# football_main_board_2016.net
KiCad netlist of a schematic drawn in Altium Designer
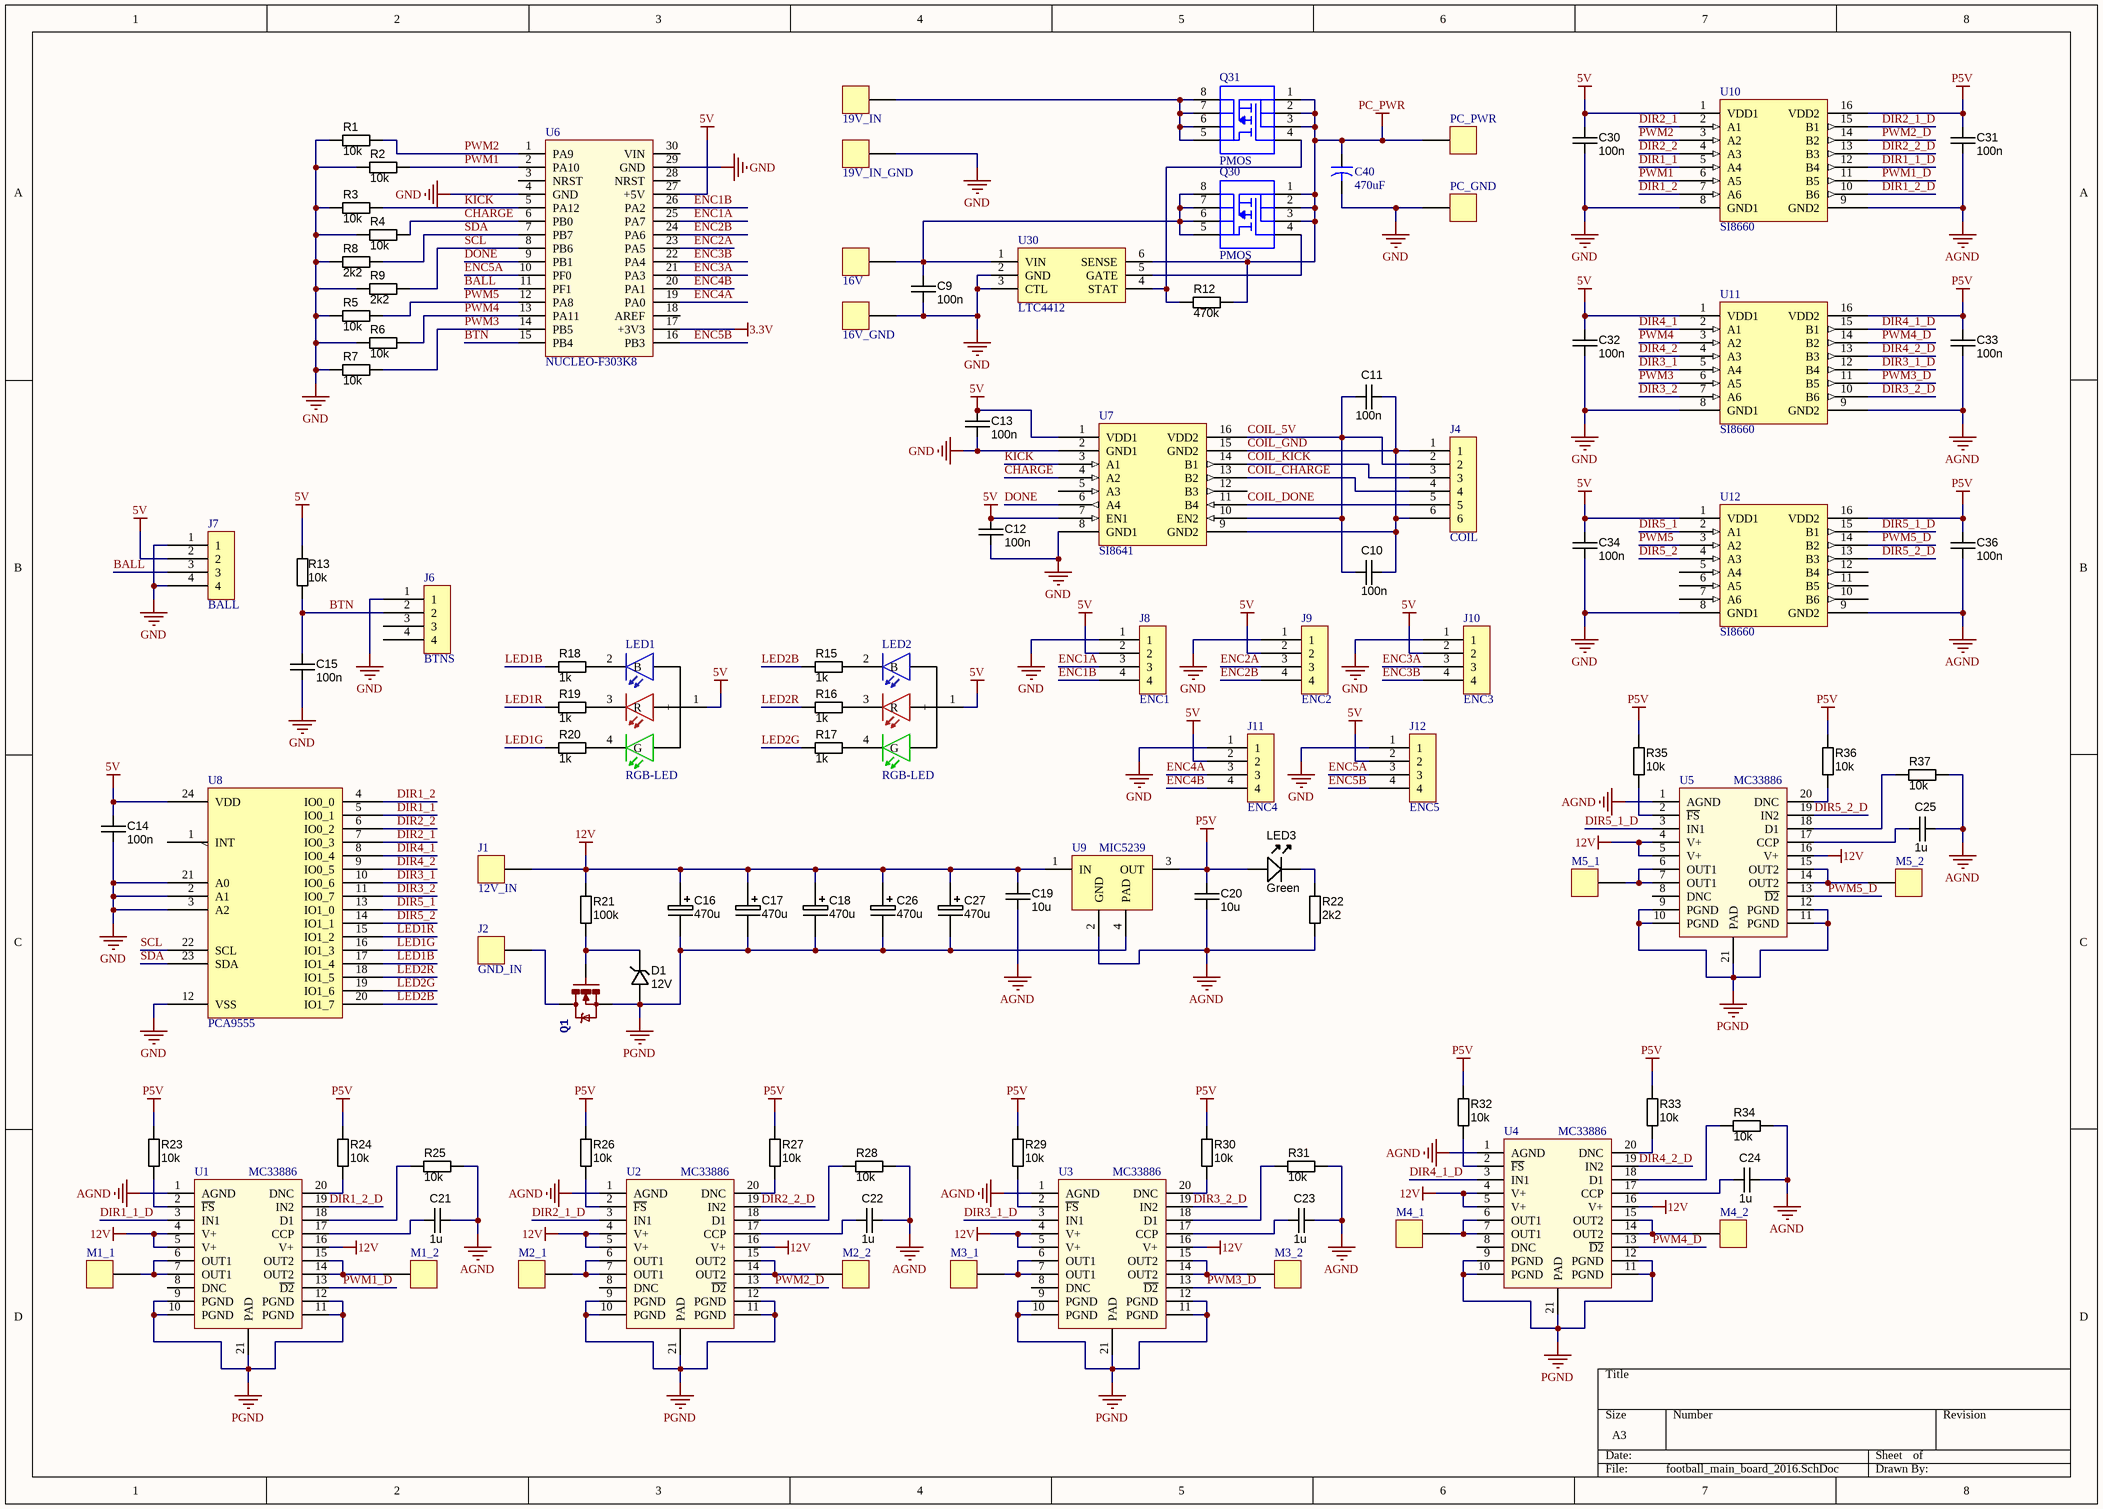
[diagram p0: football_main_board_2016.SchDoc]

(export (version "E")
  (design (tool "Eeschema 10.0.6"))
  (components
    (comp (ref "16V") (value "HEADER-1") (footprint "POWER-PAD-4x3") (libsource (lib "") (part "HEADER-1_1")))
    (comp (ref "16V_GND")
      (value "HEADER-1")
      (footprint "POWER-PAD-4x3")
      (libsource (lib "") (part "HEADER-1_1"))
    )
    (comp (ref "19V_IN")
      (value "HEADER-1")
      (footprint "POWER-PAD-4x3")
      (libsource (lib "") (part "HEADER-1_1"))
    )
    (comp (ref "19V_IN_GND")
      (value "HEADER-1")
      (footprint "POWER-PAD-4x3")
      (libsource (lib "") (part "HEADER-1_1"))
    )
    (comp (ref "C9")
      (value "100n")
      (footprint "CAPC1608X90N")
      (description "Capacitor SMD Cer 10nF 10% 50V X7R 0603")
      (fields (field (name "TOLERANCE") "±10%"))
      (libsource (lib "PBL - Capacitors") (part "CAPC_10n_0603_X7R_50V_10%"))
    )
    (comp (ref "C10")
      (value "100n")
      (footprint "CAPC1608X90N")
      (description "Capacitor SMD Cer 10nF 10% 50V X7R 0603")
      (fields (field (name "TOLERANCE") "±10%"))
      (libsource (lib "PBL - Capacitors") (part "CAPC_10n_0603_X7R_50V_10%"))
    )
    (comp (ref "C11")
      (value "100n")
      (footprint "CAPC1608X90N")
      (description "Capacitor SMD Cer 10nF 10% 50V X7R 0603")
      (fields (field (name "TOLERANCE") "±10%"))
      (libsource (lib "PBL - Capacitors") (part "CAPC_10n_0603_X7R_50V_10%"))
    )
    (comp (ref "C12")
      (value "100n")
      (footprint "CAPC1608X90N")
      (description "Capacitor SMD Cer 10nF 10% 50V X7R 0603")
      (fields (field (name "TOLERANCE") "±10%"))
      (libsource (lib "PBL - Capacitors") (part "CAPC_10n_0603_X7R_50V_10%"))
    )
    (comp (ref "C13")
      (value "100n")
      (footprint "CAPC1608X90N")
      (description "Capacitor SMD Cer 10nF 10% 50V X7R 0603")
      (fields (field (name "TOLERANCE") "±10%"))
      (libsource (lib "PBL - Capacitors") (part "CAPC_10n_0603_X7R_50V_10%"))
    )
    (comp (ref "C14")
      (value "100n")
      (footprint "CAPC1608X90N")
      (description "Capacitor SMD Cer 10nF 10% 50V X7R 0603")
      (fields (field (name "TOLERANCE") "±10%"))
      (libsource (lib "PBL - Capacitors") (part "CAPC_10n_0603_X7R_50V_10%"))
    )
    (comp (ref "C15")
      (value "100n")
      (footprint "CAPC1608X90N")
      (description "Capacitor SMD Cer 10nF 10% 50V X7R 0603")
      (fields (field (name "TOLERANCE") "±10%"))
      (libsource (lib "PBL - Capacitors") (part "CAPC_10n_0603_X7R_50V_10%"))
    )
    (comp (ref "C16")
      (value "470u")
      (footprint "CAP-LEADED-SMD-5")
      (libsource (lib "misc") (part "CAP-ELEC"))
    )
    (comp (ref "C17")
      (value "470u")
      (footprint "CAP-LEADED-SMD-5")
      (libsource (lib "misc") (part "CAP-ELEC"))
    )
    (comp (ref "C18")
      (value "470u")
      (footprint "CAP-LEADED-SMD-5")
      (libsource (lib "misc") (part "CAP-ELEC"))
    )
    (comp (ref "C19")
      (value "10u")
      (footprint "CAPC3216X180N")
      (description "Capacitor SMD Cer 10uF 10% 16V X7R 1206")
      (fields (field (name "TOLERANCE") "±10%"))
      (libsource (lib "PBL - Capacitors") (part "CAPC_10u_1206_16V"))
    )
    (comp (ref "C20")
      (value "10u")
      (footprint "CAPC3216X180N")
      (description "Capacitor SMD Cer 10uF 10% 16V X7R 1206")
      (fields (field (name "TOLERANCE") "±10%"))
      (libsource (lib "PBL - Capacitors") (part "CAPC_10u_1206_16V"))
    )
    (comp (ref "C21")
      (value "1u")
      (footprint "CAPC1608X90N")
      (description "Capacitor SMD Cer 10nF 10% 50V X7R 0603")
      (fields (field (name "TOLERANCE") "±10%"))
      (libsource (lib "PBL - Capacitors") (part "CAPC_10n_0603_X7R_50V_10%"))
    )
    (comp (ref "C22")
      (value "1u")
      (footprint "CAPC1608X90N")
      (description "Capacitor SMD Cer 10nF 10% 50V X7R 0603")
      (fields (field (name "TOLERANCE") "±10%"))
      (libsource (lib "PBL - Capacitors") (part "CAPC_10n_0603_X7R_50V_10%"))
    )
    (comp (ref "C23")
      (value "1u")
      (footprint "CAPC1608X90N")
      (description "Capacitor SMD Cer 10nF 10% 50V X7R 0603")
      (fields (field (name "TOLERANCE") "±10%"))
      (libsource (lib "PBL - Capacitors") (part "CAPC_10n_0603_X7R_50V_10%"))
    )
    (comp (ref "C24")
      (value "1u")
      (footprint "CAPC1608X90N")
      (description "Capacitor SMD Cer 10nF 10% 50V X7R 0603")
      (fields (field (name "TOLERANCE") "±10%"))
      (libsource (lib "PBL - Capacitors") (part "CAPC_10n_0603_X7R_50V_10%"))
    )
    (comp (ref "C25")
      (value "1u")
      (footprint "CAPC1608X90N")
      (description "Capacitor SMD Cer 10nF 10% 50V X7R 0603")
      (fields (field (name "TOLERANCE") "±10%"))
      (libsource (lib "PBL - Capacitors") (part "CAPC_10n_0603_X7R_50V_10%"))
    )
    (comp (ref "C26")
      (value "470u")
      (footprint "CAP-LEADED-SMD-5")
      (libsource (lib "misc") (part "CAP-ELEC"))
    )
    (comp (ref "C27")
      (value "470u")
      (footprint "CAP-LEADED-SMD-5")
      (libsource (lib "misc") (part "CAP-ELEC"))
    )
    (comp (ref "C30")
      (value "100n")
      (footprint "CAPC1608X90N")
      (description "Capacitor SMD Cer 10nF 10% 50V X7R 0603")
      (fields (field (name "TOLERANCE") "±10%"))
      (libsource (lib "PBL - Capacitors") (part "CAPC_10n_0603_X7R_50V_10%"))
    )
    (comp (ref "C31")
      (value "100n")
      (footprint "CAPC1608X90N")
      (description "Capacitor SMD Cer 10nF 10% 50V X7R 0603")
      (fields (field (name "TOLERANCE") "±10%"))
      (libsource (lib "PBL - Capacitors") (part "CAPC_10n_0603_X7R_50V_10%"))
    )
    (comp (ref "C32")
      (value "100n")
      (footprint "CAPC1608X90N")
      (description "Capacitor SMD Cer 10nF 10% 50V X7R 0603")
      (fields (field (name "TOLERANCE") "±10%"))
      (libsource (lib "PBL - Capacitors") (part "CAPC_10n_0603_X7R_50V_10%"))
    )
    (comp (ref "C33")
      (value "100n")
      (footprint "CAPC1608X90N")
      (description "Capacitor SMD Cer 10nF 10% 50V X7R 0603")
      (fields (field (name "TOLERANCE") "±10%"))
      (libsource (lib "PBL - Capacitors") (part "CAPC_10n_0603_X7R_50V_10%"))
    )
    (comp (ref "C34")
      (value "100n")
      (footprint "CAPC1608X90N")
      (description "Capacitor SMD Cer 10nF 10% 50V X7R 0603")
      (fields (field (name "TOLERANCE") "±10%"))
      (libsource (lib "PBL - Capacitors") (part "CAPC_10n_0603_X7R_50V_10%"))
    )
    (comp (ref "C36")
      (value "100n")
      (footprint "CAPC1608X90N")
      (description "Capacitor SMD Cer 10nF 10% 50V X7R 0603")
      (fields (field (name "TOLERANCE") "±10%"))
      (libsource (lib "PBL - Capacitors") (part "CAPC_10n_0603_X7R_50V_10%"))
    )
    (comp (ref "C40")
      (value "470uF")
      (footprint "CAPR5-4X5")
      (description "Capacitor")
      (fields (field (name "PUBLISHER") "Altium Limited"))
      (libsource (lib "Miscellaneous Devices") (part "Cap2"))
    )
    (comp (ref "D1")
      (value "12V")
      (footprint "SOD123")
      (description "Diode Zener SMD 28V 0.5W SOD-123")
      (fields (field (name "TOLERANCE") "±5%"))
      (libsource (lib "PBL - Diodes") (part "DIODE_ZENER_28V_500mW"))
    )
    (comp (ref "J1") (value "12V_IN") (footprint "POWER-PAD") (libsource (lib "") (part "HEADER-1_1")))
    (comp (ref "J2") (value "GND_IN") (footprint "POWER-PAD") (libsource (lib "") (part "HEADER-1_1")))
    (comp (ref "J4")
      (value "COIL")
      (footprint "MICRO-MATCH-6")
      (libsource (lib "connectors") (part "HEADER-6"))
    )
    (comp (ref "J6")
      (value "BTNS")
      (footprint "MICRO-MATCH-4")
      (libsource (lib "connectors") (part "HEADER-4"))
    )
    (comp (ref "J7")
      (value "BALL")
      (footprint "MICRO-MATCH-4")
      (libsource (lib "connectors") (part "HEADER-4"))
    )
    (comp (ref "J8")
      (value "ENC1")
      (footprint "MICRO-MATCH-4")
      (libsource (lib "connectors") (part "HEADER-4"))
    )
    (comp (ref "J9")
      (value "ENC2")
      (footprint "MICRO-MATCH-4")
      (libsource (lib "connectors") (part "HEADER-4"))
    )
    (comp (ref "J10")
      (value "ENC3")
      (footprint "MICRO-MATCH-4")
      (libsource (lib "connectors") (part "HEADER-4"))
    )
    (comp (ref "J11")
      (value "ENC4")
      (footprint "MICRO-MATCH-4")
      (libsource (lib "connectors") (part "HEADER-4"))
    )
    (comp (ref "J12")
      (value "ENC5")
      (footprint "MICRO-MATCH-4")
      (libsource (lib "connectors") (part "HEADER-4"))
    )
    (comp (ref "LED1") (value "RGB-LED") (footprint "RGB-LED") (libsource (lib "misc") (part "RGB-LED")))
    (comp (ref "LED2") (value "RGB-LED") (footprint "RGB-LED") (libsource (lib "misc") (part "RGB-LED")))
    (comp (ref "LED3")
      (value "Green")
      (footprint "LED-0603-GREEN")
      (description "LED 0603 SMD Green 570nm 50mcd 20mA")
      (libsource (lib "PBL - Light Sources") (part "LED_SMD_Green_0603_570nm"))
    )
    (comp (ref "M1_1")
      (value "HEADER-1")
      (footprint "POWER-PAD-4x3")
      (libsource (lib "") (part "HEADER-1_1"))
    )
    (comp (ref "M1_2")
      (value "HEADER-1")
      (footprint "POWER-PAD-4x3")
      (libsource (lib "connectors") (part "HEADER-1"))
    )
    (comp (ref "M2_1")
      (value "HEADER-1")
      (footprint "POWER-PAD-4x3")
      (libsource (lib "") (part "HEADER-1_1"))
    )
    (comp (ref "M2_2")
      (value "HEADER-1")
      (footprint "POWER-PAD-4x3")
      (libsource (lib "connectors") (part "HEADER-1"))
    )
    (comp (ref "M3_1")
      (value "HEADER-1")
      (footprint "POWER-PAD-4x3")
      (libsource (lib "") (part "HEADER-1_1"))
    )
    (comp (ref "M3_2")
      (value "HEADER-1")
      (footprint "POWER-PAD-4x3")
      (libsource (lib "connectors") (part "HEADER-1"))
    )
    (comp (ref "M4_1")
      (value "HEADER-1")
      (footprint "POWER-PAD-4x3")
      (libsource (lib "") (part "HEADER-1_1"))
    )
    (comp (ref "M4_2")
      (value "HEADER-1")
      (footprint "POWER-PAD-4x3")
      (libsource (lib "connectors") (part "HEADER-1"))
    )
    (comp (ref "M5_1")
      (value "HEADER-1")
      (footprint "POWER-PAD-4x3")
      (libsource (lib "") (part "HEADER-1_1"))
    )
    (comp (ref "M5_2")
      (value "HEADER-1")
      (footprint "POWER-PAD-4x3")
      (libsource (lib "connectors") (part "HEADER-1"))
    )
    (comp (ref "PC_GND")
      (value "HEADER-1")
      (footprint "POWER-PAD-4x3")
      (libsource (lib "connectors") (part "HEADER-1"))
    )
    (comp (ref "PC_PWR")
      (value "HEADER-1")
      (footprint "POWER-PAD-4x3")
      (libsource (lib "connectors") (part "HEADER-1"))
    )
    (comp (ref "Q1") (value "MOSFET-N") (footprint "SOT669") (libsource (lib "mosfets") (part "MOSFET-N")))
    (comp (ref "Q30") (value "PMOS") (footprint "SO8") (libsource (lib "misc") (part "PMOS")))
    (comp (ref "Q31") (value "PMOS") (footprint "SO8") (libsource (lib "misc") (part "PMOS")))
    (comp (ref "R1")
      (value "10k")
      (footprint "RESC1608X55N")
      (description "Resistor SMD chip 10k Ohm 0.1W 1% 0603")
      (fields (field (name "TOLERANCE") "±1%"))
      (libsource (lib "PBL - Resistors") (part "RES_10K_0603_1%"))
    )
    (comp (ref "R2")
      (value "10k")
      (footprint "RESC1608X55N")
      (description "Resistor SMD chip 10k Ohm 0.1W 1% 0603")
      (fields (field (name "TOLERANCE") "±1%"))
      (libsource (lib "PBL - Resistors") (part "RES_10K_0603_1%"))
    )
    (comp (ref "R3")
      (value "10k")
      (footprint "RESC1608X55N")
      (description "Resistor SMD chip 10k Ohm 0.1W 1% 0603")
      (fields (field (name "TOLERANCE") "±1%"))
      (libsource (lib "PBL - Resistors") (part "RES_10K_0603_1%"))
    )
    (comp (ref "R4")
      (value "10k")
      (footprint "RESC1608X55N")
      (description "Resistor SMD chip 10k Ohm 0.1W 1% 0603")
      (fields (field (name "TOLERANCE") "±1%"))
      (libsource (lib "PBL - Resistors") (part "RES_10K_0603_1%"))
    )
    (comp (ref "R5")
      (value "10k")
      (footprint "RESC1608X55N")
      (description "Resistor SMD chip 10k Ohm 0.1W 1% 0603")
      (fields (field (name "TOLERANCE") "±1%"))
      (libsource (lib "PBL - Resistors") (part "RES_10K_0603_1%"))
    )
    (comp (ref "R6")
      (value "10k")
      (footprint "RESC1608X55N")
      (description "Resistor SMD chip 10k Ohm 0.1W 1% 0603")
      (fields (field (name "TOLERANCE") "±1%"))
      (libsource (lib "PBL - Resistors") (part "RES_10K_0603_1%"))
    )
    (comp (ref "R7")
      (value "10k")
      (footprint "RESC1608X55N")
      (description "Resistor SMD chip 10k Ohm 0.1W 1% 0603")
      (fields (field (name "TOLERANCE") "±1%"))
      (libsource (lib "PBL - Resistors") (part "RES_10K_0603_1%"))
    )
    (comp (ref "R8")
      (value "2k2")
      (footprint "RESC1608X55N")
      (description "Resistor SMD chip 10k Ohm 0.1W 1% 0603")
      (fields (field (name "TOLERANCE") "±1%"))
      (libsource (lib "PBL - Resistors") (part "RES_10K_0603_1%"))
    )
    (comp (ref "R9")
      (value "2k2")
      (footprint "RESC1608X55N")
      (description "Resistor SMD chip 10k Ohm 0.1W 1% 0603")
      (fields (field (name "TOLERANCE") "±1%"))
      (libsource (lib "PBL - Resistors") (part "RES_10K_0603_1%"))
    )
    (comp (ref "R12")
      (value "470k")
      (footprint "RESC1608N_ZERO")
      (description "Resistor SMD chip 0.0 Ohm 0.1W 0603")
      (fields (field (name "TOLERANCE") "±5%"))
      (libsource (lib "PBL - Resistors") (part "RES_0R_0603"))
    )
    (comp (ref "R13")
      (value "10k")
      (footprint "RESC1608N_ZERO")
      (description "Resistor SMD chip 0.0 Ohm 0.1W 0603")
      (fields (field (name "TOLERANCE") "±5%"))
      (libsource (lib "") (part "RES_0R_0603_1"))
    )
    (comp (ref "R15")
      (value "1k")
      (footprint "RESC1608N_ZERO")
      (description "Resistor SMD chip 0.0 Ohm 0.1W 0603")
      (fields (field (name "TOLERANCE") "±5%"))
      (libsource (lib "PBL - Resistors") (part "RES_0R_0603"))
    )
    (comp (ref "R16")
      (value "1k")
      (footprint "RESC1608N_ZERO")
      (description "Resistor SMD chip 0.0 Ohm 0.1W 0603")
      (fields (field (name "TOLERANCE") "±5%"))
      (libsource (lib "PBL - Resistors") (part "RES_0R_0603"))
    )
    (comp (ref "R17")
      (value "1k")
      (footprint "RESC1608N_ZERO")
      (description "Resistor SMD chip 0.0 Ohm 0.1W 0603")
      (fields (field (name "TOLERANCE") "±5%"))
      (libsource (lib "PBL - Resistors") (part "RES_0R_0603"))
    )
    (comp (ref "R18")
      (value "1k")
      (footprint "RESC1608N_ZERO")
      (description "Resistor SMD chip 0.0 Ohm 0.1W 0603")
      (fields (field (name "TOLERANCE") "±5%"))
      (libsource (lib "PBL - Resistors") (part "RES_0R_0603"))
    )
    (comp (ref "R19")
      (value "1k")
      (footprint "RESC1608N_ZERO")
      (description "Resistor SMD chip 0.0 Ohm 0.1W 0603")
      (fields (field (name "TOLERANCE") "±5%"))
      (libsource (lib "PBL - Resistors") (part "RES_0R_0603"))
    )
    (comp (ref "R20")
      (value "1k")
      (footprint "RESC1608N_ZERO")
      (description "Resistor SMD chip 0.0 Ohm 0.1W 0603")
      (fields (field (name "TOLERANCE") "±5%"))
      (libsource (lib "PBL - Resistors") (part "RES_0R_0603"))
    )
    (comp (ref "R21")
      (value "100k")
      (footprint "RESC1608X55N")
      (description "Resistor SMD chip 1k Ohm 0.1W 1% 0603")
      (fields (field (name "TOLERANCE") "±1%"))
      (libsource (lib "") (part "RES_1K_0603_1%_1"))
    )
    (comp (ref "R22")
      (value "2k2")
      (footprint "RESC1608X55N")
      (description "Resistor SMD chip 1k Ohm 0.1W 1% 0603")
      (fields (field (name "TOLERANCE") "±1%"))
      (libsource (lib "") (part "RES_1K_0603_1%_1"))
    )
    (comp (ref "R23")
      (value "10k")
      (footprint "RESC1608X55N")
      (description "Resistor SMD chip 1k Ohm 0.1W 1% 0603")
      (fields (field (name "TOLERANCE") "±1%"))
      (libsource (lib "") (part "RES_1K_0603_1%_1"))
    )
    (comp (ref "R24")
      (value "10k")
      (footprint "RESC1608X55N")
      (description "Resistor SMD chip 1k Ohm 0.1W 1% 0603")
      (fields (field (name "TOLERANCE") "±1%"))
      (libsource (lib "") (part "RES_1K_0603_1%_1"))
    )
    (comp (ref "R25")
      (value "10k")
      (footprint "RESC1608X55N")
      (description "Resistor SMD chip 1k Ohm 0.1W 1% 0603")
      (fields (field (name "TOLERANCE") "±1%"))
      (libsource (lib "PBL - Resistors") (part "RES_1K_0603_1%"))
    )
    (comp (ref "R26")
      (value "10k")
      (footprint "RESC1608X55N")
      (description "Resistor SMD chip 1k Ohm 0.1W 1% 0603")
      (fields (field (name "TOLERANCE") "±1%"))
      (libsource (lib "") (part "RES_1K_0603_1%_1"))
    )
    (comp (ref "R27")
      (value "10k")
      (footprint "RESC1608X55N")
      (description "Resistor SMD chip 1k Ohm 0.1W 1% 0603")
      (fields (field (name "TOLERANCE") "±1%"))
      (libsource (lib "") (part "RES_1K_0603_1%_1"))
    )
    (comp (ref "R28")
      (value "10k")
      (footprint "RESC1608X55N")
      (description "Resistor SMD chip 1k Ohm 0.1W 1% 0603")
      (fields (field (name "TOLERANCE") "±1%"))
      (libsource (lib "PBL - Resistors") (part "RES_1K_0603_1%"))
    )
    (comp (ref "R29")
      (value "10k")
      (footprint "RESC1608X55N")
      (description "Resistor SMD chip 1k Ohm 0.1W 1% 0603")
      (fields (field (name "TOLERANCE") "±1%"))
      (libsource (lib "") (part "RES_1K_0603_1%_1"))
    )
    (comp (ref "R30")
      (value "10k")
      (footprint "RESC1608X55N")
      (description "Resistor SMD chip 1k Ohm 0.1W 1% 0603")
      (fields (field (name "TOLERANCE") "±1%"))
      (libsource (lib "") (part "RES_1K_0603_1%_1"))
    )
    (comp (ref "R31")
      (value "10k")
      (footprint "RESC1608X55N")
      (description "Resistor SMD chip 1k Ohm 0.1W 1% 0603")
      (fields (field (name "TOLERANCE") "±1%"))
      (libsource (lib "PBL - Resistors") (part "RES_1K_0603_1%"))
    )
    (comp (ref "R32")
      (value "10k")
      (footprint "RESC1608X55N")
      (description "Resistor SMD chip 1k Ohm 0.1W 1% 0603")
      (fields (field (name "TOLERANCE") "±1%"))
      (libsource (lib "") (part "RES_1K_0603_1%_1"))
    )
    (comp (ref "R33")
      (value "10k")
      (footprint "RESC1608X55N")
      (description "Resistor SMD chip 1k Ohm 0.1W 1% 0603")
      (fields (field (name "TOLERANCE") "±1%"))
      (libsource (lib "") (part "RES_1K_0603_1%_1"))
    )
    (comp (ref "R34")
      (value "10k")
      (footprint "RESC1608X55N")
      (description "Resistor SMD chip 1k Ohm 0.1W 1% 0603")
      (fields (field (name "TOLERANCE") "±1%"))
      (libsource (lib "PBL - Resistors") (part "RES_1K_0603_1%"))
    )
    (comp (ref "R35")
      (value "10k")
      (footprint "RESC1608X55N")
      (description "Resistor SMD chip 1k Ohm 0.1W 1% 0603")
      (fields (field (name "TOLERANCE") "±1%"))
      (libsource (lib "") (part "RES_1K_0603_1%_1"))
    )
    (comp (ref "R36")
      (value "10k")
      (footprint "RESC1608X55N")
      (description "Resistor SMD chip 1k Ohm 0.1W 1% 0603")
      (fields (field (name "TOLERANCE") "±1%"))
      (libsource (lib "") (part "RES_1K_0603_1%_1"))
    )
    (comp (ref "R37")
      (value "10k")
      (footprint "RESC1608X55N")
      (description "Resistor SMD chip 1k Ohm 0.1W 1% 0603")
      (fields (field (name "TOLERANCE") "±1%"))
      (libsource (lib "PBL - Resistors") (part "RES_1K_0603_1%"))
    )
    (comp (ref "U1")
      (value "MC33886")
      (footprint "MC33886")
      (libsource (lib "motor_drivers") (part "MC33886"))
    )
    (comp (ref "U2")
      (value "MC33886")
      (footprint "MC33886")
      (libsource (lib "motor_drivers") (part "MC33886"))
    )
    (comp (ref "U3")
      (value "MC33886")
      (footprint "MC33886")
      (libsource (lib "motor_drivers") (part "MC33886"))
    )
    (comp (ref "U4")
      (value "MC33886")
      (footprint "MC33886")
      (libsource (lib "motor_drivers") (part "MC33886"))
    )
    (comp (ref "U5")
      (value "MC33886")
      (footprint "MC33886")
      (libsource (lib "motor_drivers") (part "MC33886"))
    )
    (comp (ref "U6")
      (value "NUCLEO-F303K8")
      (footprint "NUCLEO-F303K8")
      (libsource (lib "mbed") (part "NUCLEO-F303K8"))
    )
    (comp (ref "U7") (value "SI8641") (footprint "SOIC16") (libsource (lib "digital") (part "SI8641")))
    (comp (ref "U8") (value "PCA9555") (footprint "TSSOP24") (libsource (lib "digital") (part "PCA9555")))
    (comp (ref "U9")
      (value "MIC5239")
      (footprint "SOT230P700X180-4N")
      (libsource (lib "power") (part "MIC5239"))
    )
    (comp (ref "U10") (value "SI8660") (footprint "SOIC16") (libsource (lib "digital") (part "SI8660")))
    (comp (ref "U11") (value "SI8660") (footprint "SOIC16") (libsource (lib "digital") (part "SI8660")))
    (comp (ref "U12") (value "SI8660") (footprint "SOIC16") (libsource (lib "digital") (part "SI8660")))
    (comp (ref "U30") (value "LTC4412") (footprint "TSOT-23-6") (libsource (lib "digital") (part "LTC4412")))
  )
  (nets
    (net (code "1") (name "/BALL") (class "Default")
      (node (ref "J7") (pin "3") (pinfunction "3_3") (pintype "passive"))
      (node (ref "U6") (pin "11") (pinfunction "PF1_11") (pintype "passive"))
    )
    (net (code "2") (name "/BTN") (class "Default")
      (node (ref "C15") (pin "1") (pintype "passive"))
      (node (ref "J6") (pin "2") (pinfunction "2_2") (pintype "passive"))
      (node (ref "R13") (pin "1") (pinfunction "1_1") (pintype "passive"))
      (node (ref "U6") (pin "15") (pinfunction "PB4_15") (pintype "passive"))
    )
    (net (code "3") (name "/CHARGE") (class "Default")
      (node (ref "R4") (pin "2") (pinfunction "2_2") (pintype "passive"))
      (node (ref "U6") (pin "6") (pinfunction "PB0_6") (pintype "passive"))
      (node (ref "U7") (pin "4") (pinfunction "A2_4") (pintype "input"))
    )
    (net (code "4") (name "/COIL_5V") (class "Default")
      (node (ref "C10") (pin "1") (pintype "passive"))
      (node (ref "C11") (pin "1") (pintype "passive"))
      (node (ref "J4") (pin "2") (pinfunction "2_2") (pintype "passive"))
      (node (ref "U7") (pin "10") (pinfunction "EN2_10") (pintype "input"))
      (node (ref "U7") (pin "16") (pinfunction "VDD2_16") (pintype "power_in"))
    )
    (net (code "5") (name "/COIL_CHARGE") (class "Default")
      (node (ref "J4") (pin "4") (pinfunction "4_4") (pintype "passive"))
      (node (ref "U7") (pin "13") (pinfunction "B2_13") (pintype "output"))
    )
    (net (code "6") (name "/COIL_DONE") (class "Default")
      (node (ref "J4") (pin "5") (pinfunction "5_5") (pintype "passive"))
      (node (ref "U7") (pin "11") (pinfunction "B4_11") (pintype "input"))
    )
    (net (code "7") (name "/COIL_GND") (class "Default")
      (node (ref "C10") (pin "2") (pintype "passive"))
      (node (ref "C11") (pin "2") (pintype "passive"))
      (node (ref "J4") (pin "1") (pinfunction "1_1") (pintype "passive"))
      (node (ref "J4") (pin "6") (pinfunction "6_6") (pintype "passive"))
      (node (ref "U7") (pin "15") (pinfunction "GND2_15") (pintype "power_in"))
      (node (ref "U7") (pin "9") (pinfunction "GND2_9") (pintype "power_in"))
    )
    (net (code "8") (name "/COIL_KICK") (class "Default")
      (node (ref "J4") (pin "3") (pinfunction "3_3") (pintype "passive"))
      (node (ref "U7") (pin "14") (pinfunction "B1_14") (pintype "output"))
    )
    (net (code "9") (name "/DIR1_1") (class "Default")
      (node (ref "U10") (pin "5") (pinfunction "A4_5") (pintype "input"))
      (node (ref "U8") (pin "5") (pinfunction "IO0_1_5") (pintype "passive"))
    )
    (net (code "10") (name "/DIR1_1_D") (class "Default")
      (node (ref "U1") (pin "3") (pinfunction "IN1_3") (pintype "passive"))
      (node (ref "U10") (pin "12") (pinfunction "B4_12") (pintype "output"))
    )
    (net (code "11") (name "/DIR1_2") (class "Default")
      (node (ref "U10") (pin "7") (pinfunction "A6_7") (pintype "input"))
      (node (ref "U8") (pin "4") (pinfunction "IO0_0_4") (pintype "passive"))
    )
    (net (code "12") (name "/DIR1_2_D") (class "Default")
      (node (ref "U1") (pin "19") (pinfunction "IN2_19") (pintype "passive"))
      (node (ref "U10") (pin "10") (pinfunction "B6_10") (pintype "output"))
    )
    (net (code "13") (name "/DIR2_1") (class "Default")
      (node (ref "U10") (pin "2") (pinfunction "A1_2") (pintype "input"))
      (node (ref "U8") (pin "7") (pinfunction "IO0_3_7") (pintype "passive"))
    )
    (net (code "14") (name "/DIR2_1_D") (class "Default")
      (node (ref "U10") (pin "15") (pinfunction "B1_15") (pintype "output"))
      (node (ref "U2") (pin "3") (pinfunction "IN1_3") (pintype "passive"))
    )
    (net (code "15") (name "/DIR2_2") (class "Default")
      (node (ref "U10") (pin "4") (pinfunction "A3_4") (pintype "input"))
      (node (ref "U8") (pin "6") (pinfunction "IO0_2_6") (pintype "passive"))
    )
    (net (code "16") (name "/DIR2_2_D") (class "Default")
      (node (ref "U10") (pin "13") (pinfunction "B3_13") (pintype "output"))
      (node (ref "U2") (pin "19") (pinfunction "IN2_19") (pintype "passive"))
    )
    (net (code "17") (name "/DIR3_1") (class "Default")
      (node (ref "U11") (pin "5") (pinfunction "A4_5") (pintype "input"))
      (node (ref "U8") (pin "10") (pinfunction "IO0_6_10") (pintype "passive"))
    )
    (net (code "18") (name "/DIR3_1_D") (class "Default")
      (node (ref "U11") (pin "12") (pinfunction "B4_12") (pintype "output"))
      (node (ref "U3") (pin "3") (pinfunction "IN1_3") (pintype "passive"))
    )
    (net (code "19") (name "/DIR3_2") (class "Default")
      (node (ref "U11") (pin "7") (pinfunction "A6_7") (pintype "input"))
      (node (ref "U8") (pin "11") (pinfunction "IO0_7_11") (pintype "passive"))
    )
    (net (code "20") (name "/DIR3_2_D") (class "Default")
      (node (ref "U11") (pin "10") (pinfunction "B6_10") (pintype "output"))
      (node (ref "U3") (pin "19") (pinfunction "IN2_19") (pintype "passive"))
    )
    (net (code "21") (name "/DIR4_1") (class "Default")
      (node (ref "U11") (pin "2") (pinfunction "A1_2") (pintype "input"))
      (node (ref "U8") (pin "8") (pinfunction "IO0_4_8") (pintype "passive"))
    )
    (net (code "22") (name "/DIR4_1_D") (class "Default")
      (node (ref "U11") (pin "15") (pinfunction "B1_15") (pintype "output"))
      (node (ref "U4") (pin "3") (pinfunction "IN1_3") (pintype "passive"))
    )
    (net (code "23") (name "/DIR4_2") (class "Default")
      (node (ref "U11") (pin "4") (pinfunction "A3_4") (pintype "input"))
      (node (ref "U8") (pin "9") (pinfunction "IO0_5_9") (pintype "passive"))
    )
    (net (code "24") (name "/DIR4_2_D") (class "Default")
      (node (ref "U11") (pin "13") (pinfunction "B3_13") (pintype "output"))
      (node (ref "U4") (pin "19") (pinfunction "IN2_19") (pintype "passive"))
    )
    (net (code "25") (name "/DIR5_1") (class "Default")
      (node (ref "U12") (pin "2") (pinfunction "A1_2") (pintype "input"))
      (node (ref "U8") (pin "13") (pinfunction "IO1_0_13") (pintype "passive"))
    )
    (net (code "26") (name "/DIR5_1_D") (class "Default")
      (node (ref "U12") (pin "15") (pinfunction "B1_15") (pintype "output"))
      (node (ref "U5") (pin "3") (pinfunction "IN1_3") (pintype "passive"))
    )
    (net (code "27") (name "/DIR5_2") (class "Default")
      (node (ref "U12") (pin "4") (pinfunction "A3_4") (pintype "input"))
      (node (ref "U8") (pin "14") (pinfunction "IO1_1_14") (pintype "passive"))
    )
    (net (code "28") (name "/DIR5_2_D") (class "Default")
      (node (ref "U12") (pin "13") (pinfunction "B3_13") (pintype "output"))
      (node (ref "U5") (pin "19") (pinfunction "IN2_19") (pintype "passive"))
    )
    (net (code "29") (name "/DONE") (class "Default")
      (node (ref "U6") (pin "9") (pinfunction "PB1_9") (pintype "passive"))
      (node (ref "U7") (pin "6") (pinfunction "A4_6") (pintype "output"))
    )
    (net (code "30") (name "/ENC1A") (class "Default")
      (node (ref "J8") (pin "3") (pinfunction "3_3") (pintype "passive"))
      (node (ref "U6") (pin "25") (pinfunction "PA7_25") (pintype "passive"))
    )
    (net (code "31") (name "/ENC1B") (class "Default")
      (node (ref "J8") (pin "4") (pinfunction "4_4") (pintype "passive"))
      (node (ref "U6") (pin "26") (pinfunction "PA2_26") (pintype "passive"))
    )
    (net (code "32") (name "/ENC2A") (class "Default")
      (node (ref "J9") (pin "3") (pinfunction "3_3") (pintype "passive"))
      (node (ref "U6") (pin "23") (pinfunction "PA5_23") (pintype "passive"))
    )
    (net (code "33") (name "/ENC2B") (class "Default")
      (node (ref "J9") (pin "4") (pinfunction "4_4") (pintype "passive"))
      (node (ref "U6") (pin "24") (pinfunction "PA6_24") (pintype "passive"))
    )
    (net (code "34") (name "/ENC3A") (class "Default")
      (node (ref "J10") (pin "3") (pinfunction "3_3") (pintype "passive"))
      (node (ref "U6") (pin "21") (pinfunction "PA3_21") (pintype "passive"))
    )
    (net (code "35") (name "/ENC3B") (class "Default")
      (node (ref "J10") (pin "4") (pinfunction "4_4") (pintype "passive"))
      (node (ref "U6") (pin "22") (pinfunction "PA4_22") (pintype "passive"))
    )
    (net (code "36") (name "/ENC4A") (class "Default")
      (node (ref "J11") (pin "3") (pinfunction "3_3") (pintype "passive"))
      (node (ref "U6") (pin "19") (pinfunction "PA0_19") (pintype "passive"))
    )
    (net (code "37") (name "/ENC4B") (class "Default")
      (node (ref "J11") (pin "4") (pinfunction "4_4") (pintype "passive"))
      (node (ref "U6") (pin "20") (pinfunction "PA1_20") (pintype "passive"))
    )
    (net (code "38") (name "/ENC5A") (class "Default")
      (node (ref "J12") (pin "3") (pinfunction "3_3") (pintype "passive"))
      (node (ref "U6") (pin "10") (pinfunction "PF0_10") (pintype "passive"))
    )
    (net (code "39") (name "/ENC5B") (class "Default")
      (node (ref "J12") (pin "4") (pinfunction "4_4") (pintype "passive"))
      (node (ref "U6") (pin "16") (pinfunction "PB3_16") (pintype "passive"))
    )
    (net (code "40") (name "/KICK") (class "Default")
      (node (ref "R3") (pin "2") (pinfunction "2_2") (pintype "passive"))
      (node (ref "U6") (pin "5") (pinfunction "PA12_5") (pintype "passive"))
      (node (ref "U7") (pin "3") (pinfunction "A1_3") (pintype "input"))
    )
    (net (code "41") (name "/LED1B") (class "Default")
      (node (ref "R18") (pin "2") (pinfunction "2_2") (pintype "passive"))
      (node (ref "U8") (pin "17") (pinfunction "IO1_4_17") (pintype "passive"))
    )
    (net (code "42") (name "/LED1G") (class "Default")
      (node (ref "R20") (pin "2") (pinfunction "2_2") (pintype "passive"))
      (node (ref "U8") (pin "16") (pinfunction "IO1_3_16") (pintype "passive"))
    )
    (net (code "43") (name "/LED1R") (class "Default")
      (node (ref "R19") (pin "2") (pinfunction "2_2") (pintype "passive"))
      (node (ref "U8") (pin "15") (pinfunction "IO1_2_15") (pintype "passive"))
    )
    (net (code "44") (name "/LED2B") (class "Default")
      (node (ref "R15") (pin "2") (pinfunction "2_2") (pintype "passive"))
      (node (ref "U8") (pin "20") (pinfunction "IO1_7_20") (pintype "passive"))
    )
    (net (code "45") (name "/LED2G") (class "Default")
      (node (ref "R17") (pin "2") (pinfunction "2_2") (pintype "passive"))
      (node (ref "U8") (pin "19") (pinfunction "IO1_6_19") (pintype "passive"))
    )
    (net (code "46") (name "/LED2R") (class "Default")
      (node (ref "R16") (pin "2") (pinfunction "2_2") (pintype "passive"))
      (node (ref "U8") (pin "18") (pinfunction "IO1_5_18") (pintype "passive"))
    )
    (net (code "47") (name "/PWM1") (class "Default")
      (node (ref "R2") (pin "2") (pinfunction "2_2") (pintype "passive"))
      (node (ref "U10") (pin "6") (pinfunction "A5_6") (pintype "input"))
      (node (ref "U6") (pin "2") (pinfunction "PA10_2") (pintype "passive"))
    )
    (net (code "48") (name "/PWM1_D") (class "Default")
      (node (ref "U1") (pin "13") (pinfunction "~{D2}_13") (pintype "passive"))
      (node (ref "U10") (pin "11") (pinfunction "B5_11") (pintype "output"))
    )
    (net (code "49") (name "/PWM2") (class "Default")
      (node (ref "R1") (pin "2") (pinfunction "2_2") (pintype "passive"))
      (node (ref "U10") (pin "3") (pinfunction "A2_3") (pintype "input"))
      (node (ref "U6") (pin "1") (pinfunction "PA9_1") (pintype "passive"))
    )
    (net (code "50") (name "/PWM2_D") (class "Default")
      (node (ref "U10") (pin "14") (pinfunction "B2_14") (pintype "output"))
      (node (ref "U2") (pin "13") (pinfunction "~{D2}_13") (pintype "passive"))
    )
    (net (code "51") (name "/PWM3") (class "Default")
      (node (ref "R7") (pin "2") (pinfunction "2_2") (pintype "passive"))
      (node (ref "U11") (pin "6") (pinfunction "A5_6") (pintype "input"))
      (node (ref "U6") (pin "14") (pinfunction "PB5_14") (pintype "passive"))
    )
    (net (code "52") (name "/PWM3_D") (class "Default")
      (node (ref "U11") (pin "11") (pinfunction "B5_11") (pintype "output"))
      (node (ref "U3") (pin "13") (pinfunction "~{D2}_13") (pintype "passive"))
    )
    (net (code "53") (name "/PWM4") (class "Default")
      (node (ref "R6") (pin "2") (pinfunction "2_2") (pintype "passive"))
      (node (ref "U11") (pin "3") (pinfunction "A2_3") (pintype "input"))
      (node (ref "U6") (pin "13") (pinfunction "PA11_13") (pintype "passive"))
    )
    (net (code "54") (name "/PWM4_D") (class "Default")
      (node (ref "U11") (pin "14") (pinfunction "B2_14") (pintype "output"))
      (node (ref "U4") (pin "13") (pinfunction "~{D2}_13") (pintype "passive"))
    )
    (net (code "55") (name "/PWM5") (class "Default")
      (node (ref "R5") (pin "2") (pinfunction "2_2") (pintype "passive"))
      (node (ref "U12") (pin "3") (pinfunction "A2_3") (pintype "input"))
      (node (ref "U6") (pin "12") (pinfunction "PA8_12") (pintype "passive"))
    )
    (net (code "56") (name "/PWM5_D") (class "Default")
      (node (ref "U12") (pin "14") (pinfunction "B2_14") (pintype "output"))
      (node (ref "U5") (pin "13") (pinfunction "~{D2}_13") (pintype "passive"))
    )
    (net (code "57") (name "/SCL") (class "Default")
      (node (ref "R9") (pin "2") (pinfunction "2_2") (pintype "passive"))
      (node (ref "U6") (pin "8") (pinfunction "PB6_8") (pintype "passive"))
      (node (ref "U8") (pin "22") (pinfunction "SCL_22") (pintype "passive"))
    )
    (net (code "58") (name "/SDA") (class "Default")
      (node (ref "R8") (pin "2") (pinfunction "2_2") (pintype "passive"))
      (node (ref "U6") (pin "7") (pinfunction "PB7_7") (pintype "passive"))
      (node (ref "U8") (pin "23") (pinfunction "SDA_23") (pintype "passive"))
    )
    (net (code "59") (name "3.3V") (class "Default")
      (node (ref "U6") (pin "17") (pinfunction "+3V3_17") (pintype "passive"))
    )
    (net (code "60") (name "5V") (class "Default")
      (node (ref "C12") (pin "2") (pintype "passive"))
      (node (ref "C13") (pin "1") (pintype "passive"))
      (node (ref "C14") (pin "2") (pintype "passive"))
      (node (ref "C30") (pin "1") (pintype "passive"))
      (node (ref "C32") (pin "1") (pintype "passive"))
      (node (ref "C34") (pin "1") (pintype "passive"))
      (node (ref "J10") (pin "2") (pinfunction "2_2") (pintype "passive"))
      (node (ref "J11") (pin "2") (pinfunction "2_2") (pintype "passive"))
      (node (ref "J12") (pin "2") (pinfunction "2_2") (pintype "passive"))
      (node (ref "J7") (pin "2") (pinfunction "2_2") (pintype "passive"))
      (node (ref "J8") (pin "2") (pinfunction "2_2") (pintype "passive"))
      (node (ref "J9") (pin "2") (pinfunction "2_2") (pintype "passive"))
      (node (ref "LED1") (pin "1") (pinfunction "+_1") (pintype "passive"))
      (node (ref "LED2") (pin "1") (pinfunction "+_1") (pintype "passive"))
      (node (ref "R13") (pin "2") (pinfunction "2_2") (pintype "passive"))
      (node (ref "U10") (pin "1") (pinfunction "VDD1_1") (pintype "power_in"))
      (node (ref "U11") (pin "1") (pinfunction "VDD1_1") (pintype "power_in"))
      (node (ref "U12") (pin "1") (pinfunction "VDD1_1") (pintype "power_in"))
      (node (ref "U6") (pin "27") (pinfunction "+5V_27") (pintype "passive"))
      (node (ref "U7") (pin "1") (pinfunction "VDD1_1") (pintype "power_in"))
      (node (ref "U7") (pin "7") (pinfunction "EN1_7") (pintype "input"))
      (node (ref "U8") (pin "24") (pinfunction "VDD_24") (pintype "passive"))
    )
    (net (code "61") (name "12V") (class "Default")
      (node (ref "C16") (pin "1") (pinfunction "1_1") (pintype "passive"))
      (node (ref "C17") (pin "1") (pinfunction "1_1") (pintype "passive"))
      (node (ref "C18") (pin "1") (pinfunction "1_1") (pintype "passive"))
      (node (ref "C19") (pin "1") (pintype "passive"))
      (node (ref "C26") (pin "1") (pinfunction "1_1") (pintype "passive"))
      (node (ref "C27") (pin "1") (pinfunction "1_1") (pintype "passive"))
      (node (ref "J1") (pin "1") (pinfunction "1_1") (pintype "passive"))
      (node (ref "R21") (pin "1") (pinfunction "1_1") (pintype "passive"))
      (node (ref "U1") (pin "16") (pinfunction "V+_16") (pintype "passive"))
      (node (ref "U1") (pin "4") (pinfunction "V+_4") (pintype "passive"))
      (node (ref "U1") (pin "5") (pinfunction "V+_5") (pintype "passive"))
      (node (ref "U2") (pin "16") (pinfunction "V+_16") (pintype "passive"))
      (node (ref "U2") (pin "4") (pinfunction "V+_4") (pintype "passive"))
      (node (ref "U2") (pin "5") (pinfunction "V+_5") (pintype "passive"))
      (node (ref "U3") (pin "16") (pinfunction "V+_16") (pintype "passive"))
      (node (ref "U3") (pin "4") (pinfunction "V+_4") (pintype "passive"))
      (node (ref "U3") (pin "5") (pinfunction "V+_5") (pintype "passive"))
      (node (ref "U4") (pin "16") (pinfunction "V+_16") (pintype "passive"))
      (node (ref "U4") (pin "4") (pinfunction "V+_4") (pintype "passive"))
      (node (ref "U4") (pin "5") (pinfunction "V+_5") (pintype "passive"))
      (node (ref "U5") (pin "16") (pinfunction "V+_16") (pintype "passive"))
      (node (ref "U5") (pin "4") (pinfunction "V+_4") (pintype "passive"))
      (node (ref "U5") (pin "5") (pinfunction "V+_5") (pintype "passive"))
      (node (ref "U9") (pin "1") (pinfunction "IN_1") (pintype "power_in"))
    )
    (net (code "62") (name "AGND") (class "Default")
      (node (ref "C19") (pin "2") (pintype "passive"))
      (node (ref "C20") (pin "2") (pintype "passive"))
      (node (ref "C21") (pin "2") (pintype "passive"))
      (node (ref "C22") (pin "2") (pintype "passive"))
      (node (ref "C23") (pin "2") (pintype "passive"))
      (node (ref "C24") (pin "2") (pintype "passive"))
      (node (ref "C25") (pin "2") (pintype "passive"))
      (node (ref "C31") (pin "2") (pintype "passive"))
      (node (ref "C33") (pin "2") (pintype "passive"))
      (node (ref "C36") (pin "2") (pintype "passive"))
      (node (ref "R22") (pin "2") (pinfunction "2_2") (pintype "passive"))
      (node (ref "R25") (pin "2") (pinfunction "2_2") (pintype "passive"))
      (node (ref "R28") (pin "2") (pinfunction "2_2") (pintype "passive"))
      (node (ref "R31") (pin "2") (pinfunction "2_2") (pintype "passive"))
      (node (ref "R34") (pin "2") (pinfunction "2_2") (pintype "passive"))
      (node (ref "R37") (pin "2") (pinfunction "2_2") (pintype "passive"))
      (node (ref "U1") (pin "1") (pinfunction "AGND_1") (pintype "passive"))
      (node (ref "U10") (pin "9") (pinfunction "GND2_9") (pintype "power_in"))
      (node (ref "U11") (pin "9") (pinfunction "GND2_9") (pintype "power_in"))
      (node (ref "U12") (pin "9") (pinfunction "GND2_9") (pintype "power_in"))
      (node (ref "U2") (pin "1") (pinfunction "AGND_1") (pintype "passive"))
      (node (ref "U3") (pin "1") (pinfunction "AGND_1") (pintype "passive"))
      (node (ref "U4") (pin "1") (pinfunction "AGND_1") (pintype "passive"))
      (node (ref "U5") (pin "1") (pinfunction "AGND_1") (pintype "passive"))
      (node (ref "U9") (pin "2") (pinfunction "GND_2") (pintype "power_in"))
    )
    (net (code "63") (name "GND") (class "Default")
      (node (ref "16V_GND") (pin "1") (pinfunction "1_1") (pintype "passive"))
      (node (ref "19V_IN_GND") (pin "1") (pinfunction "1_1") (pintype "passive"))
      (node (ref "C12") (pin "1") (pintype "passive"))
      (node (ref "C13") (pin "2") (pintype "passive"))
      (node (ref "C14") (pin "1") (pintype "passive"))
      (node (ref "C15") (pin "2") (pintype "passive"))
      (node (ref "C30") (pin "2") (pintype "passive"))
      (node (ref "C32") (pin "2") (pintype "passive"))
      (node (ref "C34") (pin "2") (pintype "passive"))
      (node (ref "C40") (pin "2") (pinfunction "2_2") (pintype "passive"))
      (node (ref "C9") (pin "2") (pintype "passive"))
      (node (ref "J10") (pin "1") (pinfunction "1_1") (pintype "passive"))
      (node (ref "J11") (pin "1") (pinfunction "1_1") (pintype "passive"))
      (node (ref "J12") (pin "1") (pinfunction "1_1") (pintype "passive"))
      (node (ref "J6") (pin "1") (pinfunction "1_1") (pintype "passive"))
      (node (ref "J7") (pin "1") (pinfunction "1_1") (pintype "passive"))
      (node (ref "J7") (pin "4") (pinfunction "4_4") (pintype "passive"))
      (node (ref "J8") (pin "1") (pinfunction "1_1") (pintype "passive"))
      (node (ref "J9") (pin "1") (pinfunction "1_1") (pintype "passive"))
      (node (ref "PC_GND") (pin "1") (pinfunction "1_1") (pintype "passive"))
      (node (ref "R1") (pin "1") (pinfunction "1_1") (pintype "passive"))
      (node (ref "R2") (pin "1") (pinfunction "1_1") (pintype "passive"))
      (node (ref "R3") (pin "1") (pinfunction "1_1") (pintype "passive"))
      (node (ref "R4") (pin "1") (pinfunction "1_1") (pintype "passive"))
      (node (ref "R5") (pin "1") (pinfunction "1_1") (pintype "passive"))
      (node (ref "R6") (pin "1") (pinfunction "1_1") (pintype "passive"))
      (node (ref "R7") (pin "1") (pinfunction "1_1") (pintype "passive"))
      (node (ref "R8") (pin "1") (pinfunction "1_1") (pintype "passive"))
      (node (ref "R9") (pin "1") (pinfunction "1_1") (pintype "passive"))
      (node (ref "U10") (pin "8") (pinfunction "GND1_8") (pintype "power_in"))
      (node (ref "U11") (pin "8") (pinfunction "GND1_8") (pintype "power_in"))
      (node (ref "U12") (pin "8") (pinfunction "GND1_8") (pintype "power_in"))
      (node (ref "U30") (pin "2") (pinfunction "GND_2") (pintype "passive"))
      (node (ref "U30") (pin "3") (pinfunction "CTL_3") (pintype "passive"))
      (node (ref "U6") (pin "29") (pinfunction "GND_29") (pintype "passive"))
      (node (ref "U6") (pin "4") (pinfunction "GND_4") (pintype "passive"))
      (node (ref "U7") (pin "2") (pinfunction "GND1_2") (pintype "power_in"))
      (node (ref "U7") (pin "8") (pinfunction "GND1_8") (pintype "power_in"))
      (node (ref "U8") (pin "12") (pinfunction "VSS_12") (pintype "passive"))
      (node (ref "U8") (pin "2") (pinfunction "A1_2") (pintype "passive"))
      (node (ref "U8") (pin "21") (pinfunction "A0_21") (pintype "passive"))
      (node (ref "U8") (pin "3") (pinfunction "A2_3") (pintype "passive"))
    )
    (net (code "64") (name "Net-(19V_IN-Pad1)") (class "Default")
      (node (ref "19V_IN") (pin "1") (pinfunction "1_1") (pintype "passive"))
      (node (ref "Q31") (pin "5") (pinfunction "5_5") (pintype "passive"))
      (node (ref "Q31") (pin "6") (pinfunction "6_6") (pintype "passive"))
      (node (ref "Q31") (pin "7") (pinfunction "7_7") (pintype "passive"))
      (node (ref "Q31") (pin "8") (pinfunction "8_8") (pintype "passive"))
    )
    (net (code "65") (name "Net-(D1-PadK)") (class "Default")
      (node (ref "D1") (pin "K") (pinfunction "K_K") (pintype "passive"))
      (node (ref "Q1") (pin "G") (pinfunction "G_G") (pintype "passive"))
      (node (ref "R21") (pin "2") (pinfunction "2_2") (pintype "passive"))
    )
    (net (code "66") (name "Net-(J2-Pad1)") (class "Default")
      (node (ref "J2") (pin "1") (pinfunction "1_1") (pintype "passive"))
      (node (ref "Q1") (pin "D") (pinfunction "D_D") (pintype "passive"))
    )
    (net (code "67") (name "Net-(LED1-B)") (class "Default")
      (node (ref "LED1") (pin "2") (pinfunction "B_2") (pintype "passive"))
      (node (ref "R18") (pin "1") (pinfunction "1_1") (pintype "passive"))
    )
    (net (code "68") (name "Net-(LED1-G)") (class "Default")
      (node (ref "LED1") (pin "4") (pinfunction "G_4") (pintype "passive"))
      (node (ref "R20") (pin "1") (pinfunction "1_1") (pintype "passive"))
    )
    (net (code "69") (name "Net-(LED1-R)") (class "Default")
      (node (ref "LED1") (pin "3") (pinfunction "R_3") (pintype "passive"))
      (node (ref "R19") (pin "1") (pinfunction "1_1") (pintype "passive"))
    )
    (net (code "70") (name "Net-(LED2-B)") (class "Default")
      (node (ref "LED2") (pin "2") (pinfunction "B_2") (pintype "passive"))
      (node (ref "R15") (pin "1") (pinfunction "1_1") (pintype "passive"))
    )
    (net (code "71") (name "Net-(LED2-G)") (class "Default")
      (node (ref "LED2") (pin "4") (pinfunction "G_4") (pintype "passive"))
      (node (ref "R17") (pin "1") (pinfunction "1_1") (pintype "passive"))
    )
    (net (code "72") (name "Net-(LED2-R)") (class "Default")
      (node (ref "LED2") (pin "3") (pinfunction "R_3") (pintype "passive"))
      (node (ref "R16") (pin "1") (pinfunction "1_1") (pintype "passive"))
    )
    (net (code "73") (name "Net-(LED3-PadK)") (class "Default")
      (node (ref "LED3") (pin "K") (pinfunction "K_K") (pintype "passive"))
      (node (ref "R22") (pin "1") (pinfunction "1_1") (pintype "passive"))
    )
    (net (code "74") (name "Net-(M1_1-Pad1)") (class "Default")
      (node (ref "M1_1") (pin "1") (pinfunction "1_1") (pintype "passive"))
      (node (ref "U1") (pin "6") (pinfunction "OUT1_6") (pintype "passive"))
      (node (ref "U1") (pin "7") (pinfunction "OUT1_7") (pintype "passive"))
    )
    (net (code "75") (name "Net-(M1_2-Pad1)") (class "Default")
      (node (ref "M1_2") (pin "1") (pinfunction "1_1") (pintype "passive"))
      (node (ref "U1") (pin "14") (pinfunction "OUT2_14") (pintype "passive"))
      (node (ref "U1") (pin "15") (pinfunction "OUT2_15") (pintype "passive"))
    )
    (net (code "76") (name "Net-(M2_1-Pad1)") (class "Default")
      (node (ref "M2_1") (pin "1") (pinfunction "1_1") (pintype "passive"))
      (node (ref "U2") (pin "6") (pinfunction "OUT1_6") (pintype "passive"))
      (node (ref "U2") (pin "7") (pinfunction "OUT1_7") (pintype "passive"))
    )
    (net (code "77") (name "Net-(M2_2-Pad1)") (class "Default")
      (node (ref "M2_2") (pin "1") (pinfunction "1_1") (pintype "passive"))
      (node (ref "U2") (pin "14") (pinfunction "OUT2_14") (pintype "passive"))
      (node (ref "U2") (pin "15") (pinfunction "OUT2_15") (pintype "passive"))
    )
    (net (code "78") (name "Net-(M3_1-Pad1)") (class "Default")
      (node (ref "M3_1") (pin "1") (pinfunction "1_1") (pintype "passive"))
      (node (ref "U3") (pin "6") (pinfunction "OUT1_6") (pintype "passive"))
      (node (ref "U3") (pin "7") (pinfunction "OUT1_7") (pintype "passive"))
    )
    (net (code "79") (name "Net-(M3_2-Pad1)") (class "Default")
      (node (ref "M3_2") (pin "1") (pinfunction "1_1") (pintype "passive"))
      (node (ref "U3") (pin "14") (pinfunction "OUT2_14") (pintype "passive"))
      (node (ref "U3") (pin "15") (pinfunction "OUT2_15") (pintype "passive"))
    )
    (net (code "80") (name "Net-(M4_1-Pad1)") (class "Default")
      (node (ref "M4_1") (pin "1") (pinfunction "1_1") (pintype "passive"))
      (node (ref "U4") (pin "6") (pinfunction "OUT1_6") (pintype "passive"))
      (node (ref "U4") (pin "7") (pinfunction "OUT1_7") (pintype "passive"))
    )
    (net (code "81") (name "Net-(M4_2-Pad1)") (class "Default")
      (node (ref "M4_2") (pin "1") (pinfunction "1_1") (pintype "passive"))
      (node (ref "U4") (pin "14") (pinfunction "OUT2_14") (pintype "passive"))
      (node (ref "U4") (pin "15") (pinfunction "OUT2_15") (pintype "passive"))
    )
    (net (code "82") (name "Net-(M5_1-Pad1)") (class "Default")
      (node (ref "M5_1") (pin "1") (pinfunction "1_1") (pintype "passive"))
      (node (ref "U5") (pin "6") (pinfunction "OUT1_6") (pintype "passive"))
      (node (ref "U5") (pin "7") (pinfunction "OUT1_7") (pintype "passive"))
    )
    (net (code "83") (name "Net-(M5_2-Pad1)") (class "Default")
      (node (ref "M5_2") (pin "1") (pinfunction "1_1") (pintype "passive"))
      (node (ref "U5") (pin "14") (pinfunction "OUT2_14") (pintype "passive"))
      (node (ref "U5") (pin "15") (pinfunction "OUT2_15") (pintype "passive"))
    )
    (net (code "84") (name "Net-(R24-Pad2)") (class "Default")
      (node (ref "R24") (pin "2") (pinfunction "2_2") (pintype "passive"))
      (node (ref "U1") (pin "20") (pinfunction "DNC_20") (pintype "passive"))
    )
    (net (code "85") (name "Net-(R27-Pad2)") (class "Default")
      (node (ref "R27") (pin "2") (pinfunction "2_2") (pintype "passive"))
      (node (ref "U2") (pin "20") (pinfunction "DNC_20") (pintype "passive"))
    )
    (net (code "86") (name "Net-(R30-Pad2)") (class "Default")
      (node (ref "R30") (pin "2") (pinfunction "2_2") (pintype "passive"))
      (node (ref "U3") (pin "20") (pinfunction "DNC_20") (pintype "passive"))
    )
    (net (code "87") (name "Net-(R33-Pad2)") (class "Default")
      (node (ref "R33") (pin "2") (pinfunction "2_2") (pintype "passive"))
      (node (ref "U4") (pin "20") (pinfunction "DNC_20") (pintype "passive"))
    )
    (net (code "88") (name "Net-(R36-Pad2)") (class "Default")
      (node (ref "R36") (pin "2") (pinfunction "2_2") (pintype "passive"))
      (node (ref "U5") (pin "20") (pinfunction "DNC_20") (pintype "passive"))
    )
    (net (code "89") (name "Net-(U1-CCP)") (class "Default")
      (node (ref "C21") (pin "1") (pintype "passive"))
      (node (ref "U1") (pin "17") (pinfunction "CCP_17") (pintype "passive"))
    )
    (net (code "90") (name "Net-(U1-D1)") (class "Default")
      (node (ref "R25") (pin "1") (pinfunction "1_1") (pintype "passive"))
      (node (ref "U1") (pin "18") (pinfunction "D1_18") (pintype "passive"))
    )
    (net (code "91") (name "Net-(U1-~{FS})") (class "Default")
      (node (ref "R23") (pin "2") (pinfunction "2_2") (pintype "passive"))
      (node (ref "U1") (pin "2") (pinfunction "~{FS}_2") (pintype "passive"))
    )
    (net (code "92") (name "Net-(U2-CCP)") (class "Default")
      (node (ref "C22") (pin "1") (pintype "passive"))
      (node (ref "U2") (pin "17") (pinfunction "CCP_17") (pintype "passive"))
    )
    (net (code "93") (name "Net-(U2-D1)") (class "Default")
      (node (ref "R28") (pin "1") (pinfunction "1_1") (pintype "passive"))
      (node (ref "U2") (pin "18") (pinfunction "D1_18") (pintype "passive"))
    )
    (net (code "94") (name "Net-(U2-~{FS})") (class "Default")
      (node (ref "R26") (pin "2") (pinfunction "2_2") (pintype "passive"))
      (node (ref "U2") (pin "2") (pinfunction "~{FS}_2") (pintype "passive"))
    )
    (net (code "95") (name "Net-(U3-CCP)") (class "Default")
      (node (ref "C23") (pin "1") (pintype "passive"))
      (node (ref "U3") (pin "17") (pinfunction "CCP_17") (pintype "passive"))
    )
    (net (code "96") (name "Net-(U3-D1)") (class "Default")
      (node (ref "R31") (pin "1") (pinfunction "1_1") (pintype "passive"))
      (node (ref "U3") (pin "18") (pinfunction "D1_18") (pintype "passive"))
    )
    (net (code "97") (name "Net-(U3-~{FS})") (class "Default")
      (node (ref "R29") (pin "2") (pinfunction "2_2") (pintype "passive"))
      (node (ref "U3") (pin "2") (pinfunction "~{FS}_2") (pintype "passive"))
    )
    (net (code "98") (name "Net-(U4-CCP)") (class "Default")
      (node (ref "C24") (pin "1") (pintype "passive"))
      (node (ref "U4") (pin "17") (pinfunction "CCP_17") (pintype "passive"))
    )
    (net (code "99") (name "Net-(U4-D1)") (class "Default")
      (node (ref "R34") (pin "1") (pinfunction "1_1") (pintype "passive"))
      (node (ref "U4") (pin "18") (pinfunction "D1_18") (pintype "passive"))
    )
    (net (code "100") (name "Net-(U4-~{FS})") (class "Default")
      (node (ref "R32") (pin "2") (pinfunction "2_2") (pintype "passive"))
      (node (ref "U4") (pin "2") (pinfunction "~{FS}_2") (pintype "passive"))
    )
    (net (code "101") (name "Net-(U5-CCP)") (class "Default")
      (node (ref "C25") (pin "1") (pintype "passive"))
      (node (ref "U5") (pin "17") (pinfunction "CCP_17") (pintype "passive"))
    )
    (net (code "102") (name "Net-(U5-D1)") (class "Default")
      (node (ref "R37") (pin "1") (pinfunction "1_1") (pintype "passive"))
      (node (ref "U5") (pin "18") (pinfunction "D1_18") (pintype "passive"))
    )
    (net (code "103") (name "Net-(U5-~{FS})") (class "Default")
      (node (ref "R35") (pin "2") (pinfunction "2_2") (pintype "passive"))
      (node (ref "U5") (pin "2") (pinfunction "~{FS}_2") (pintype "passive"))
    )
    (net (code "104") (name "Net-(U30-GATE)") (class "Default")
      (node (ref "Q30") (pin "4") (pinfunction "4_4") (pintype "passive"))
      (node (ref "U30") (pin "5") (pinfunction "GATE_5") (pintype "passive"))
    )
    (net (code "105") (name "Net-(U30-STAT)") (class "Default")
      (node (ref "Q31") (pin "4") (pinfunction "4_4") (pintype "passive"))
      (node (ref "R12") (pin "2") (pinfunction "2_2") (pintype "passive"))
      (node (ref "U30") (pin "4") (pinfunction "STAT_4") (pintype "passive"))
    )
    (net (code "106") (name "Net-(U30-VIN)") (class "Default")
      (node (ref "16V") (pin "1") (pinfunction "1_1") (pintype "passive"))
      (node (ref "C9") (pin "1") (pintype "passive"))
      (node (ref "Q30") (pin "5") (pinfunction "5_5") (pintype "passive"))
      (node (ref "Q30") (pin "6") (pinfunction "6_6") (pintype "passive"))
      (node (ref "Q30") (pin "7") (pinfunction "7_7") (pintype "passive"))
      (node (ref "Q30") (pin "8") (pinfunction "8_8") (pintype "passive"))
      (node (ref "U30") (pin "1") (pinfunction "VIN_1") (pintype "passive"))
    )
    (net (code "107") (name "P5V") (class "Default")
      (node (ref "C20") (pin "1") (pintype "passive"))
      (node (ref "C31") (pin "1") (pintype "passive"))
      (node (ref "C33") (pin "1") (pintype "passive"))
      (node (ref "C36") (pin "1") (pintype "passive"))
      (node (ref "LED3") (pin "A") (pinfunction "A_A") (pintype "passive"))
      (node (ref "R23") (pin "1") (pinfunction "1_1") (pintype "passive"))
      (node (ref "R24") (pin "1") (pinfunction "1_1") (pintype "passive"))
      (node (ref "R26") (pin "1") (pinfunction "1_1") (pintype "passive"))
      (node (ref "R27") (pin "1") (pinfunction "1_1") (pintype "passive"))
      (node (ref "R29") (pin "1") (pinfunction "1_1") (pintype "passive"))
      (node (ref "R30") (pin "1") (pinfunction "1_1") (pintype "passive"))
      (node (ref "R32") (pin "1") (pinfunction "1_1") (pintype "passive"))
      (node (ref "R33") (pin "1") (pinfunction "1_1") (pintype "passive"))
      (node (ref "R35") (pin "1") (pinfunction "1_1") (pintype "passive"))
      (node (ref "R36") (pin "1") (pinfunction "1_1") (pintype "passive"))
      (node (ref "U10") (pin "16") (pinfunction "VDD2_16") (pintype "power_in"))
      (node (ref "U11") (pin "16") (pinfunction "VDD2_16") (pintype "power_in"))
      (node (ref "U12") (pin "16") (pinfunction "VDD2_16") (pintype "power_in"))
      (node (ref "U9") (pin "3") (pinfunction "OUT_3") (pintype "power_in"))
    )
    (net (code "108") (name "PC_PWR") (class "Default")
      (node (ref "C40") (pin "1") (pinfunction "1_1") (pintype "passive"))
      (node (ref "PC_PWR") (pin "1") (pinfunction "1_1") (pintype "passive"))
      (node (ref "Q30") (pin "1") (pinfunction "1_1") (pintype "passive"))
      (node (ref "Q30") (pin "2") (pinfunction "2_2") (pintype "passive"))
      (node (ref "Q30") (pin "3") (pinfunction "3_3") (pintype "passive"))
      (node (ref "Q31") (pin "1") (pinfunction "1_1") (pintype "passive"))
      (node (ref "Q31") (pin "2") (pinfunction "2_2") (pintype "passive"))
      (node (ref "Q31") (pin "3") (pinfunction "3_3") (pintype "passive"))
      (node (ref "R12") (pin "1") (pinfunction "1_1") (pintype "passive"))
      (node (ref "U30") (pin "6") (pinfunction "SENSE_6") (pintype "passive"))
    )
    (net (code "109") (name "PGND") (class "Default")
      (node (ref "C16") (pin "2") (pinfunction "2_2") (pintype "passive"))
      (node (ref "C17") (pin "2") (pinfunction "2_2") (pintype "passive"))
      (node (ref "C18") (pin "2") (pinfunction "2_2") (pintype "passive"))
      (node (ref "C26") (pin "2") (pinfunction "2_2") (pintype "passive"))
      (node (ref "C27") (pin "2") (pinfunction "2_2") (pintype "passive"))
      (node (ref "D1") (pin "A") (pinfunction "A_A") (pintype "passive"))
      (node (ref "Q1") (pin "S") (pinfunction "S_S") (pintype "passive"))
      (node (ref "U1") (pin "10") (pinfunction "PGND_10") (pintype "passive"))
      (node (ref "U1") (pin "11") (pinfunction "PGND_11") (pintype "passive"))
      (node (ref "U1") (pin "12") (pinfunction "PGND_12") (pintype "passive"))
      (node (ref "U1") (pin "21") (pinfunction "PAD_21") (pintype "passive"))
      (node (ref "U1") (pin "9") (pinfunction "PGND_9") (pintype "passive"))
      (node (ref "U2") (pin "10") (pinfunction "PGND_10") (pintype "passive"))
      (node (ref "U2") (pin "11") (pinfunction "PGND_11") (pintype "passive"))
      (node (ref "U2") (pin "12") (pinfunction "PGND_12") (pintype "passive"))
      (node (ref "U2") (pin "21") (pinfunction "PAD_21") (pintype "passive"))
      (node (ref "U2") (pin "9") (pinfunction "PGND_9") (pintype "passive"))
      (node (ref "U3") (pin "10") (pinfunction "PGND_10") (pintype "passive"))
      (node (ref "U3") (pin "11") (pinfunction "PGND_11") (pintype "passive"))
      (node (ref "U3") (pin "12") (pinfunction "PGND_12") (pintype "passive"))
      (node (ref "U3") (pin "21") (pinfunction "PAD_21") (pintype "passive"))
      (node (ref "U3") (pin "9") (pinfunction "PGND_9") (pintype "passive"))
      (node (ref "U4") (pin "10") (pinfunction "PGND_10") (pintype "passive"))
      (node (ref "U4") (pin "11") (pinfunction "PGND_11") (pintype "passive"))
      (node (ref "U4") (pin "12") (pinfunction "PGND_12") (pintype "passive"))
      (node (ref "U4") (pin "21") (pinfunction "PAD_21") (pintype "passive"))
      (node (ref "U4") (pin "9") (pinfunction "PGND_9") (pintype "passive"))
      (node (ref "U5") (pin "10") (pinfunction "PGND_10") (pintype "passive"))
      (node (ref "U5") (pin "11") (pinfunction "PGND_11") (pintype "passive"))
      (node (ref "U5") (pin "12") (pinfunction "PGND_12") (pintype "passive"))
      (node (ref "U5") (pin "21") (pinfunction "PAD_21") (pintype "passive"))
      (node (ref "U5") (pin "9") (pinfunction "PGND_9") (pintype "passive"))
      (node (ref "U9") (pin "4") (pinfunction "PAD_4") (pintype "power_in"))
    )
    (net (code "110") (name "unconnected-(J6-Pad3)") (class "Default")
      (node (ref "J6") (pin "3") (pinfunction "3_3") (pintype "passive"))
    )
    (net (code "111") (name "unconnected-(J6-Pad4)") (class "Default")
      (node (ref "J6") (pin "4") (pinfunction "4_4") (pintype "passive"))
    )
    (net (code "112") (name "unconnected-(U1-DNC-Pad8)") (class "Default")
      (node (ref "U1") (pin "8") (pinfunction "DNC_8") (pintype "passive"))
    )
    (net (code "113") (name "unconnected-(U2-DNC-Pad8)") (class "Default")
      (node (ref "U2") (pin "8") (pinfunction "DNC_8") (pintype "passive"))
    )
    (net (code "114") (name "unconnected-(U3-DNC-Pad8)") (class "Default")
      (node (ref "U3") (pin "8") (pinfunction "DNC_8") (pintype "passive"))
    )
    (net (code "115") (name "unconnected-(U4-DNC-Pad8)") (class "Default")
      (node (ref "U4") (pin "8") (pinfunction "DNC_8") (pintype "passive"))
    )
    (net (code "116") (name "unconnected-(U5-DNC-Pad8)") (class "Default")
      (node (ref "U5") (pin "8") (pinfunction "DNC_8") (pintype "passive"))
    )
    (net (code "117") (name "unconnected-(U6-AREF-Pad18)") (class "Default")
      (node (ref "U6") (pin "18") (pinfunction "AREF_18") (pintype "passive"))
    )
    (net (code "118") (name "unconnected-(U6-NRST-Pad3)") (class "Default")
      (node (ref "U6") (pin "3") (pinfunction "NRST_3") (pintype "passive"))
    )
    (net (code "119") (name "unconnected-(U6-NRST-Pad28)") (class "Default")
      (node (ref "U6") (pin "28") (pinfunction "NRST_28") (pintype "passive"))
    )
    (net (code "120") (name "unconnected-(U6-VIN-Pad30)") (class "Default")
      (node (ref "U6") (pin "30") (pinfunction "VIN_30") (pintype "passive"))
    )
    (net (code "121") (name "unconnected-(U7-A3-Pad5)") (class "Default")
      (node (ref "U7") (pin "5") (pinfunction "A3_5") (pintype "input"))
    )
    (net (code "122") (name "unconnected-(U7-B3-Pad12)") (class "Default")
      (node (ref "U7") (pin "12") (pinfunction "B3_12") (pintype "output"))
    )
    (net (code "123") (name "unconnected-(U8-INT-Pad1)") (class "Default")
      (node (ref "U8") (pin "1") (pinfunction "INT_1") (pintype "open_collector"))
    )
    (net (code "124") (name "unconnected-(U12-A4-Pad5)") (class "Default")
      (node (ref "U12") (pin "5") (pinfunction "A4_5") (pintype "input"))
    )
    (net (code "125") (name "unconnected-(U12-A5-Pad6)") (class "Default")
      (node (ref "U12") (pin "6") (pinfunction "A5_6") (pintype "input"))
    )
    (net (code "126") (name "unconnected-(U12-A6-Pad7)") (class "Default")
      (node (ref "U12") (pin "7") (pinfunction "A6_7") (pintype "input"))
    )
    (net (code "127") (name "unconnected-(U12-B4-Pad12)") (class "Default")
      (node (ref "U12") (pin "12") (pinfunction "B4_12") (pintype "output"))
    )
    (net (code "128") (name "unconnected-(U12-B5-Pad11)") (class "Default")
      (node (ref "U12") (pin "11") (pinfunction "B5_11") (pintype "output"))
    )
    (net (code "129") (name "unconnected-(U12-B6-Pad10)") (class "Default")
      (node (ref "U12") (pin "10") (pinfunction "B6_10") (pintype "output"))
    )
  )
)
